# Kar_PCB.net
KiCad netlist of a schematic drawn in Altium Designer
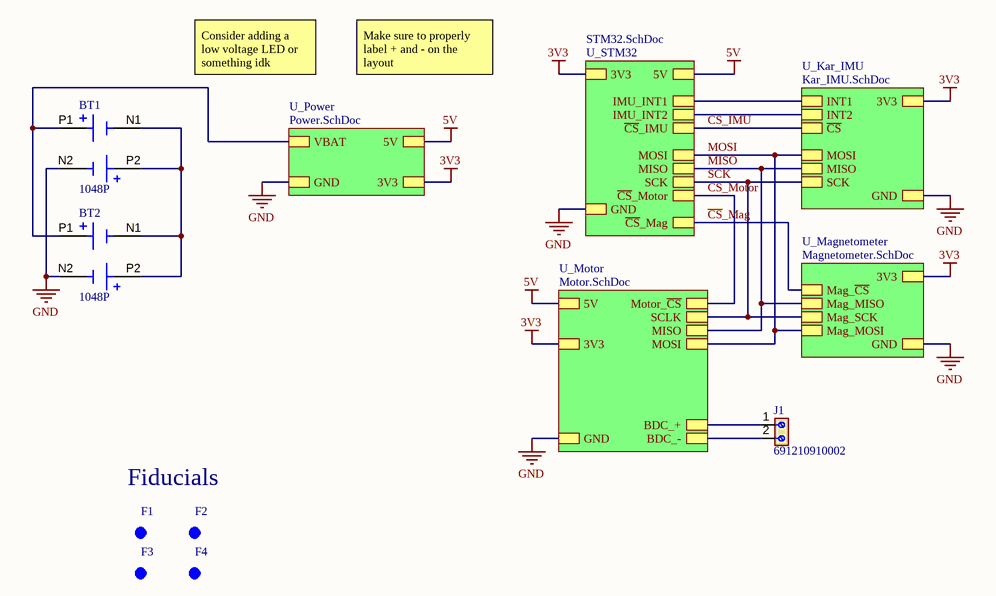
[diagram p0: Kar_PCB.SchDoc]

(export (version "E")
  (design (tool "Eeschema 10.0.6"))
  (components
    (comp (ref "BT1")
      (value "1048P")
      (footprint "BAT_1048P")
      (description "SMT Polarized Holder for Dual 18650 Batteries")
      (fields (field (name "MF") "Keystone Electronics"))
      (libsource (lib "1048P") (part "1048P"))
    )
    (comp (ref "BT2")
      (value "1048P")
      (footprint "BAT_1048P")
      (description "SMT Polarized Holder for Dual 18650 Batteries")
      (fields (field (name "MF") "Keystone Electronics"))
      (libsource (lib "1048P") (part "1048P"))
    )
    (comp (ref "F1")
      (value "Fiducial")
      (footprint "Fiducial_Footprint")
      (libsource (lib "Fiducial_lib") (part "Fiducial"))
    )
    (comp (ref "F2")
      (value "Fiducial")
      (footprint "Fiducial_Footprint")
      (libsource (lib "Fiducial_lib") (part "Fiducial"))
    )
    (comp (ref "F3")
      (value "Fiducial")
      (footprint "Fiducial_Footprint")
      (libsource (lib "Fiducial_lib") (part "Fiducial"))
    )
    (comp (ref "F4")
      (value "Fiducial")
      (footprint "Fiducial_Footprint")
      (libsource (lib "Fiducial_lib") (part "Fiducial"))
    )
    (comp (ref "J1")
      (value "691210910002")
      (footprint "691210910002")
      (fields (field (name "MF") "{'manufacturer': u'~{W}xfcrth Elektronik'}"))
      (libsource (lib "691210910002") (part "691210910002"))
    )
  )
  (nets
    (net (code "1") (name "/BDC_+") (class "Default")
      (node (ref "J1") (pin "1") (pinfunction "1_1") (pintype "passive"))
    )
    (net (code "2") (name "/BDC_-") (class "Default")
      (node (ref "J1") (pin "2") (pinfunction "2_2") (pintype "passive"))
    )
    (net (code "8") (name "/VBAT") (class "Default")
      (node (ref "BT1") (pin "P1") (pinfunction "P1_P1") (pintype "passive"))
      (node (ref "BT2") (pin "P1") (pinfunction "P1_P1") (pintype "passive"))
    )
    (net (code "14") (name "GND") (class "Default")
      (node (ref "BT1") (pin "N2") (pinfunction "N2_N2") (pintype "passive"))
      (node (ref "BT2") (pin "N2") (pinfunction "N2_N2") (pintype "passive"))
    )
    (net (code "15") (name "Net-(BT1-PadN1)") (class "Default")
      (node (ref "BT1") (pin "N1") (pinfunction "N1_N1") (pintype "passive"))
      (node (ref "BT1") (pin "P2") (pinfunction "P2_P2") (pintype "passive"))
      (node (ref "BT2") (pin "N1") (pinfunction "N1_N1") (pintype "passive"))
      (node (ref "BT2") (pin "P2") (pinfunction "P2_P2") (pintype "passive"))
    )
  )
)
